# Zio_LRA_Eval_Board_V1_0.net
KiCad netlist of a schematic drawn in EAGLE
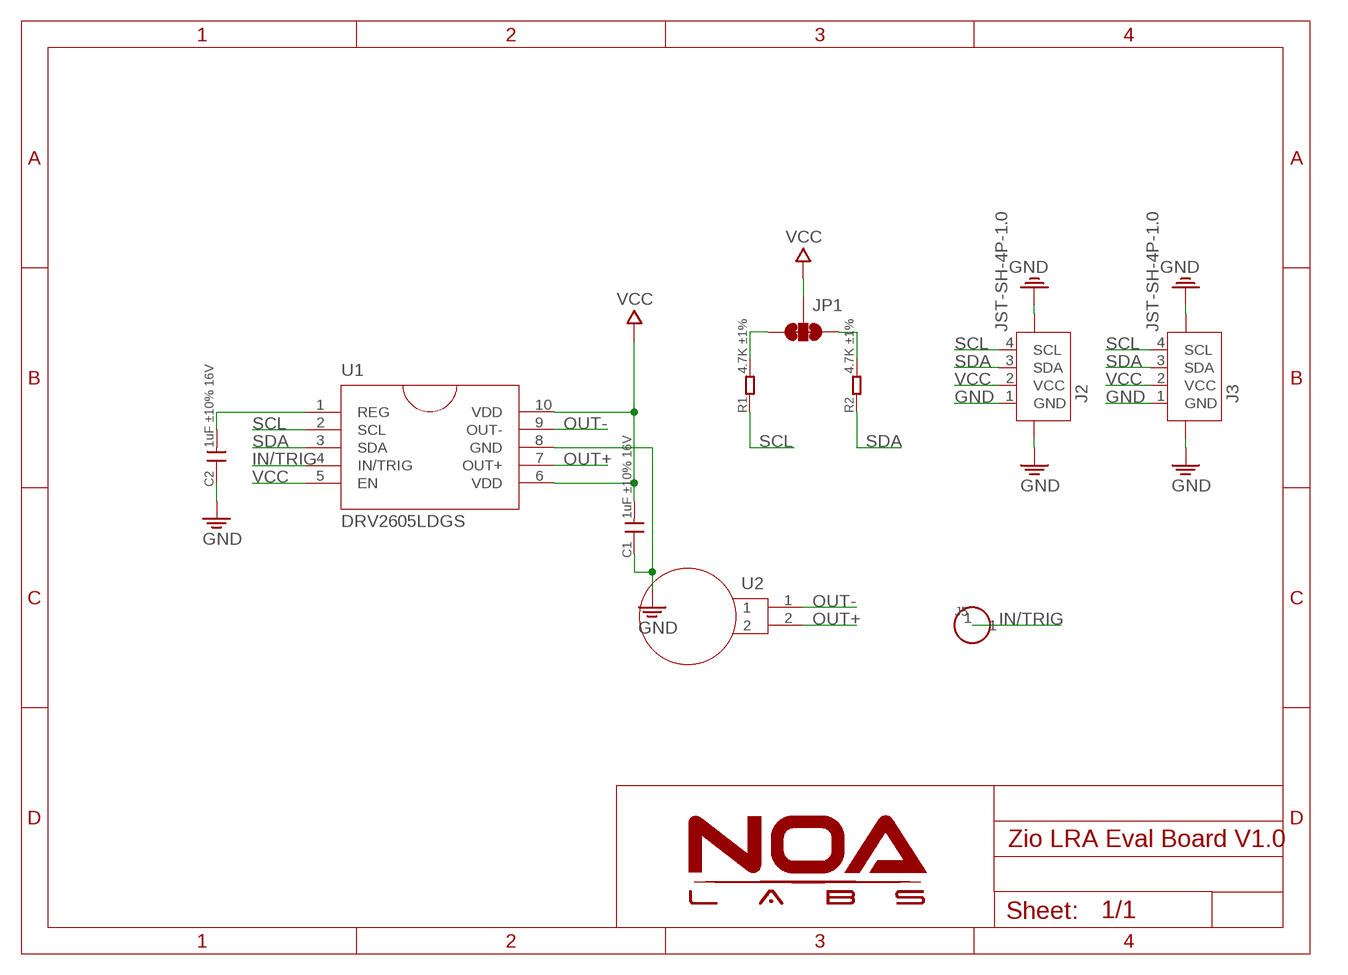
[diagram p0: schematic, sheet 1]

(export (version "E")
  (design (tool "Eeschema 10.0.6"))
  (components
    (comp (ref "C1")
      (value "1uF ±10% 16V")
      (footprint "eagle-import:C0603")
      (libsource (lib "eagle-import") (part "C-0603"))
    )
    (comp (ref "C2")
      (value "1uF ±10% 16V")
      (footprint "eagle-import:C0603")
      (libsource (lib "eagle-import") (part "C-0603"))
    )
    (comp (ref "J2")
      (value "JST-SH-4P-1.0")
      (footprint "eagle-import:JST-SH-4P")
      (libsource (lib "eagle-import") (part "JST-SH-4P-1.0"))
    )
    (comp (ref "J3")
      (value "JST-SH-4P-1.0")
      (footprint "eagle-import:JST-SH-4P")
      (libsource (lib "eagle-import") (part "JST-SH-4P-1.0"))
    )
    (comp (ref "J5")
      (value "HEADER-1P")
      (footprint "eagle-import:1P-40MIL")
      (libsource (lib "eagle-import") (part "HEADER-1P"))
    )
    (comp (ref "JP1")
      (value "SMT-JUMPER_3_2-NC_TRACE")
      (footprint "eagle-import:SMT-JUMPER_3_2-NC_TRACE")
      (libsource (lib "eagle-import") (part "SMT-JUMPER_3_2-NC_TRACE"))
    )
    (comp (ref "R1")
      (value "4.7K ±1%")
      (footprint "eagle-import:R0402")
      (libsource (lib "eagle-import") (part "R-0402"))
    )
    (comp (ref "R2")
      (value "4.7K ±1%")
      (footprint "eagle-import:R0402")
      (libsource (lib "eagle-import") (part "R-0402"))
    )
    (comp (ref "U1")
      (value "DRV2605LDGS")
      (footprint "eagle-import:VSSOP10")
      (libsource (lib "eagle-import") (part "DRV2605L"))
    )
    (comp (ref "U2")
      (value "LRA-MOTOR-081230B")
      (footprint "eagle-import:LRA-MOTOR-081230B")
      (libsource (lib "eagle-import") (part "LRA-MOTOR-081230B"))
    )
  )
  (nets
    (net (code "1") (name "/IN{slash}TRIG") (class "Default")
      (node (ref "J5") (pin "1") (pinfunction "1_1") (pintype "bidirectional"))
      (node (ref "U1") (pin "4") (pinfunction "IN/TRIG_4") (pintype "bidirectional"))
    )
    (net (code "2") (name "/OUT+") (class "Default")
      (node (ref "U1") (pin "7") (pinfunction "OUT+_7") (pintype "bidirectional"))
      (node (ref "U2") (pin "2") (pinfunction "2_2") (pintype "bidirectional"))
    )
    (net (code "3") (name "/OUT-") (class "Default")
      (node (ref "U1") (pin "9") (pinfunction "OUT-_9") (pintype "bidirectional"))
      (node (ref "U2") (pin "1") (pinfunction "1_1") (pintype "bidirectional"))
    )
    (net (code "4") (name "/SCL") (class "Default")
      (node (ref "J2") (pin "4") (pinfunction "SCL_4") (pintype "bidirectional"))
      (node (ref "J3") (pin "4") (pinfunction "SCL_4") (pintype "bidirectional"))
      (node (ref "R1") (pin "1") (pinfunction "1_1") (pintype "passive"))
      (node (ref "U1") (pin "2") (pinfunction "SCL_2") (pintype "bidirectional"))
    )
    (net (code "5") (name "/SDA") (class "Default")
      (node (ref "J2") (pin "3") (pinfunction "SDA_3") (pintype "bidirectional"))
      (node (ref "J3") (pin "3") (pinfunction "SDA_3") (pintype "bidirectional"))
      (node (ref "R2") (pin "1") (pinfunction "1_1") (pintype "passive"))
      (node (ref "U1") (pin "3") (pinfunction "SDA_3") (pintype "bidirectional"))
    )
    (net (code "6") (name "GND") (class "Default")
      (node (ref "C1") (pin "1") (pinfunction "1_1") (pintype "passive"))
      (node (ref "C2") (pin "1") (pinfunction "1_1") (pintype "passive"))
      (node (ref "J2") (pin "1") (pinfunction "GND_1") (pintype "bidirectional"))
      (node (ref "J2") (pin "NC1") (pinfunction "5_NC1") (pintype "bidirectional"))
      (node (ref "J2") (pin "NC2") (pinfunction "6_NC2") (pintype "bidirectional"))
      (node (ref "J3") (pin "1") (pinfunction "GND_1") (pintype "bidirectional"))
      (node (ref "J3") (pin "NC1") (pinfunction "5_NC1") (pintype "bidirectional"))
      (node (ref "J3") (pin "NC2") (pinfunction "6_NC2") (pintype "bidirectional"))
      (node (ref "U1") (pin "8") (pinfunction "GND_8") (pintype "bidirectional"))
    )
    (net (code "7") (name "Net-(JP1-Pad1)") (class "Default")
      (node (ref "JP1") (pin "1") (pinfunction "1_1") (pintype "passive"))
      (node (ref "R2") (pin "2") (pinfunction "2_2") (pintype "passive"))
    )
    (net (code "8") (name "Net-(JP1-Pad3)") (class "Default")
      (node (ref "JP1") (pin "3") (pinfunction "3_3") (pintype "passive"))
      (node (ref "R1") (pin "2") (pinfunction "2_2") (pintype "passive"))
    )
    (net (code "9") (name "Net-(U1-REG)") (class "Default")
      (node (ref "C2") (pin "2") (pinfunction "2_2") (pintype "passive"))
      (node (ref "U1") (pin "1") (pinfunction "REG_1") (pintype "bidirectional"))
    )
    (net (code "10") (name "VCC") (class "Default")
      (node (ref "C1") (pin "2") (pinfunction "2_2") (pintype "passive"))
      (node (ref "J2") (pin "2") (pinfunction "VCC_2") (pintype "bidirectional"))
      (node (ref "J3") (pin "2") (pinfunction "VCC_2") (pintype "bidirectional"))
      (node (ref "JP1") (pin "2") (pinfunction "2_2") (pintype "passive"))
      (node (ref "U1") (pin "10") (pinfunction "VDD_10") (pintype "bidirectional"))
      (node (ref "U1") (pin "5") (pinfunction "EN_5") (pintype "bidirectional"))
      (node (ref "U1") (pin "6") (pinfunction "VDD_6") (pintype "bidirectional"))
    )
  )
)
